# JiaB.net
KiCad netlist of a schematic drawn in EAGLE
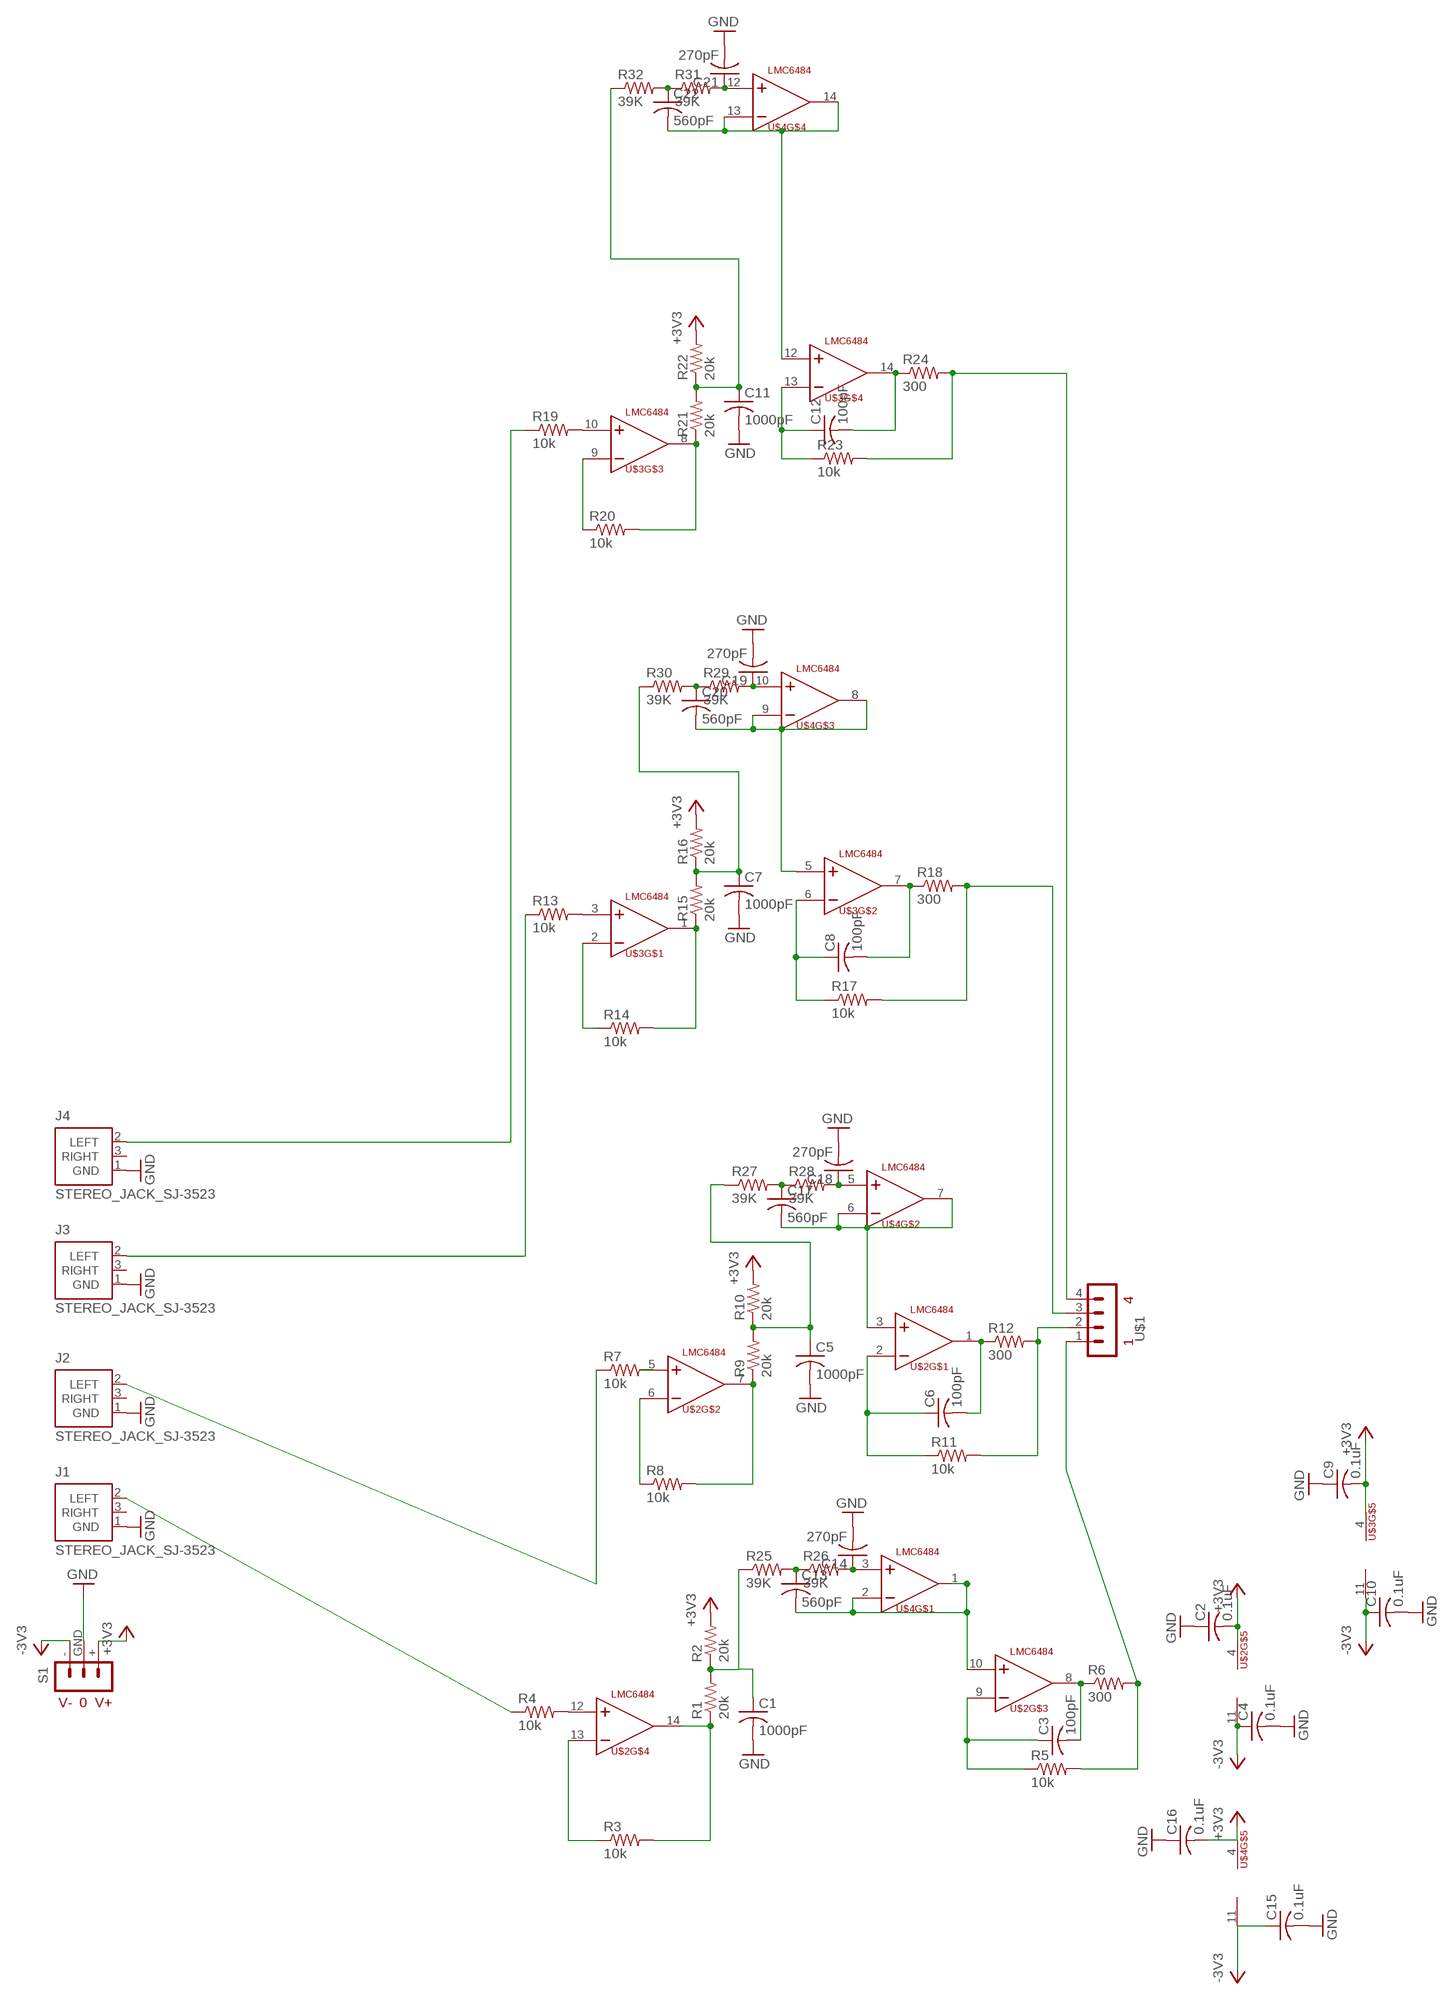
[diagram p0: schematic, sheet 1]

(export (version "E")
  (design (tool "Eeschema 10.0.6"))
  (components
    (comp (ref "C1")
      (value "1000pF")
      (footprint "eagle-import:C025-025X050")
      (libsource (lib "eagle-import") (part "resistor_C-US025-025X050"))
    )
    (comp (ref "C2")
      (value "0.1uF")
      (footprint "eagle-import:C025-025X050")
      (libsource (lib "eagle-import") (part "resistor_C-US025-025X050"))
    )
    (comp (ref "C3")
      (value "100pF")
      (footprint "eagle-import:C025-025X050")
      (libsource (lib "eagle-import") (part "resistor_C-US025-025X050"))
    )
    (comp (ref "C4")
      (value "0.1uF")
      (footprint "eagle-import:C025-025X050")
      (libsource (lib "eagle-import") (part "resistor_C-US025-025X050"))
    )
    (comp (ref "C5")
      (value "1000pF")
      (footprint "eagle-import:C025-025X050")
      (libsource (lib "eagle-import") (part "resistor_C-US025-025X050"))
    )
    (comp (ref "C6")
      (value "100pF")
      (footprint "eagle-import:C025-025X050")
      (libsource (lib "eagle-import") (part "resistor_C-US025-025X050"))
    )
    (comp (ref "C7")
      (value "1000pF")
      (footprint "eagle-import:C025-025X050")
      (libsource (lib "eagle-import") (part "resistor_C-US025-025X050"))
    )
    (comp (ref "C8")
      (value "100pF")
      (footprint "eagle-import:C025-025X050")
      (libsource (lib "eagle-import") (part "resistor_C-US025-025X050"))
    )
    (comp (ref "C9")
      (value "0.1uF")
      (footprint "eagle-import:C025-025X050")
      (libsource (lib "eagle-import") (part "resistor_C-US025-025X050"))
    )
    (comp (ref "C10")
      (value "0.1uF")
      (footprint "eagle-import:C025-025X050")
      (libsource (lib "eagle-import") (part "resistor_C-US025-025X050"))
    )
    (comp (ref "C11")
      (value "1000pF")
      (footprint "eagle-import:C025-025X050")
      (libsource (lib "eagle-import") (part "resistor_C-US025-025X050"))
    )
    (comp (ref "C12")
      (value "100pF")
      (footprint "eagle-import:C025-025X050")
      (libsource (lib "eagle-import") (part "resistor_C-US025-025X050"))
    )
    (comp (ref "C13")
      (value "560pF")
      (footprint "eagle-import:C025-025X050")
      (libsource (lib "eagle-import") (part "C-US025-025X050"))
    )
    (comp (ref "C14")
      (value "270pF")
      (footprint "eagle-import:C025-025X050")
      (libsource (lib "eagle-import") (part "C-US025-025X050"))
    )
    (comp (ref "C15")
      (value "0.1uF")
      (footprint "eagle-import:C025-025X050")
      (libsource (lib "eagle-import") (part "resistor_C-US025-025X050"))
    )
    (comp (ref "C16")
      (value "0.1uF")
      (footprint "eagle-import:C025-025X050")
      (libsource (lib "eagle-import") (part "resistor_C-US025-025X050"))
    )
    (comp (ref "C17")
      (value "560pF")
      (footprint "eagle-import:C025-025X050")
      (libsource (lib "eagle-import") (part "C-US025-025X050"))
    )
    (comp (ref "C18")
      (value "270pF")
      (footprint "eagle-import:C025-025X050")
      (libsource (lib "eagle-import") (part "C-US025-025X050"))
    )
    (comp (ref "C19")
      (value "270pF")
      (footprint "eagle-import:C025-025X050")
      (libsource (lib "eagle-import") (part "C-US025-025X050"))
    )
    (comp (ref "C20")
      (value "560pF")
      (footprint "eagle-import:C025-025X050")
      (libsource (lib "eagle-import") (part "C-US025-025X050"))
    )
    (comp (ref "C21")
      (value "270pF")
      (footprint "eagle-import:C025-025X050")
      (libsource (lib "eagle-import") (part "C-US025-025X050"))
    )
    (comp (ref "C22")
      (value "560pF")
      (footprint "eagle-import:C025-025X050")
      (libsource (lib "eagle-import") (part "C-US025-025X050"))
    )
    (comp (ref "J1")
      (value "STEREO_JACK_SJ-3523")
      (footprint "eagle-import:SJ-3523")
      (libsource (lib "eagle-import") (part "STEREO_JACK_SJ-3523"))
    )
    (comp (ref "J2")
      (value "STEREO_JACK_SJ-3523")
      (footprint "eagle-import:SJ-3523")
      (libsource (lib "eagle-import") (part "STEREO_JACK_SJ-3523"))
    )
    (comp (ref "J3")
      (value "STEREO_JACK_SJ-3523")
      (footprint "eagle-import:SJ-3523")
      (libsource (lib "eagle-import") (part "STEREO_JACK_SJ-3523"))
    )
    (comp (ref "J4")
      (value "STEREO_JACK_SJ-3523")
      (footprint "eagle-import:SJ-3523")
      (libsource (lib "eagle-import") (part "STEREO_JACK_SJ-3523"))
    )
    (comp (ref "R1")
      (value "20k")
      (footprint "eagle-import:0204_7")
      (libsource (lib "eagle-import") (part "resistor_R-US_0204/7"))
    )
    (comp (ref "R2")
      (value "20k")
      (footprint "eagle-import:0204_7")
      (libsource (lib "eagle-import") (part "resistor_R-US_0204/7"))
    )
    (comp (ref "R3")
      (value "10k")
      (footprint "eagle-import:0204_7")
      (libsource (lib "eagle-import") (part "resistor_R-US_0204/7"))
    )
    (comp (ref "R4")
      (value "10k")
      (footprint "eagle-import:0204_7")
      (libsource (lib "eagle-import") (part "resistor_R-US_0204/7"))
    )
    (comp (ref "R5")
      (value "10k")
      (footprint "eagle-import:0204_7")
      (libsource (lib "eagle-import") (part "resistor_R-US_0204/7"))
    )
    (comp (ref "R6")
      (value "300")
      (footprint "eagle-import:0204_7")
      (libsource (lib "eagle-import") (part "resistor_R-US_0204/7"))
    )
    (comp (ref "R7")
      (value "10k")
      (footprint "eagle-import:0204_7")
      (libsource (lib "eagle-import") (part "resistor_R-US_0204/7"))
    )
    (comp (ref "R8")
      (value "10k")
      (footprint "eagle-import:0204_7")
      (libsource (lib "eagle-import") (part "resistor_R-US_0204/7"))
    )
    (comp (ref "R9")
      (value "20k")
      (footprint "eagle-import:0204_7")
      (libsource (lib "eagle-import") (part "resistor_R-US_0204/7"))
    )
    (comp (ref "R10")
      (value "20k")
      (footprint "eagle-import:0204_7")
      (libsource (lib "eagle-import") (part "resistor_R-US_0204/7"))
    )
    (comp (ref "R11")
      (value "10k")
      (footprint "eagle-import:0204_7")
      (libsource (lib "eagle-import") (part "resistor_R-US_0204/7"))
    )
    (comp (ref "R12")
      (value "300")
      (footprint "eagle-import:0204_7")
      (libsource (lib "eagle-import") (part "resistor_R-US_0204/7"))
    )
    (comp (ref "R13")
      (value "10k")
      (footprint "eagle-import:0204_7")
      (libsource (lib "eagle-import") (part "resistor_R-US_0204/7"))
    )
    (comp (ref "R14")
      (value "10k")
      (footprint "eagle-import:0204_7")
      (libsource (lib "eagle-import") (part "resistor_R-US_0204/7"))
    )
    (comp (ref "R15")
      (value "20k")
      (footprint "eagle-import:0204_7")
      (libsource (lib "eagle-import") (part "resistor_R-US_0204/7"))
    )
    (comp (ref "R16")
      (value "20k")
      (footprint "eagle-import:0204_7")
      (libsource (lib "eagle-import") (part "resistor_R-US_0204/7"))
    )
    (comp (ref "R17")
      (value "10k")
      (footprint "eagle-import:0204_7")
      (libsource (lib "eagle-import") (part "resistor_R-US_0204/7"))
    )
    (comp (ref "R18")
      (value "300")
      (footprint "eagle-import:0204_7")
      (libsource (lib "eagle-import") (part "resistor_R-US_0204/7"))
    )
    (comp (ref "R19")
      (value "10k")
      (footprint "eagle-import:0204_7")
      (libsource (lib "eagle-import") (part "resistor_R-US_0204/7"))
    )
    (comp (ref "R20")
      (value "10k")
      (footprint "eagle-import:0204_7")
      (libsource (lib "eagle-import") (part "resistor_R-US_0204/7"))
    )
    (comp (ref "R21")
      (value "20k")
      (footprint "eagle-import:0204_7")
      (libsource (lib "eagle-import") (part "resistor_R-US_0204/7"))
    )
    (comp (ref "R22")
      (value "20k")
      (footprint "eagle-import:0204_7")
      (libsource (lib "eagle-import") (part "resistor_R-US_0204/7"))
    )
    (comp (ref "R23")
      (value "10k")
      (footprint "eagle-import:0204_7")
      (libsource (lib "eagle-import") (part "resistor_R-US_0204/7"))
    )
    (comp (ref "R24")
      (value "300")
      (footprint "eagle-import:0204_7")
      (libsource (lib "eagle-import") (part "resistor_R-US_0204/7"))
    )
    (comp (ref "R25")
      (value "39K")
      (footprint "eagle-import:0204_7")
      (libsource (lib "eagle-import") (part "R-US_0204/7"))
    )
    (comp (ref "R26")
      (value "39K")
      (footprint "eagle-import:0204_7")
      (libsource (lib "eagle-import") (part "R-US_0204/7"))
    )
    (comp (ref "R27")
      (value "39K")
      (footprint "eagle-import:0204_7")
      (libsource (lib "eagle-import") (part "R-US_0204/7"))
    )
    (comp (ref "R28")
      (value "39K")
      (footprint "eagle-import:0204_7")
      (libsource (lib "eagle-import") (part "R-US_0204/7"))
    )
    (comp (ref "R29")
      (value "39K")
      (footprint "eagle-import:0204_7")
      (libsource (lib "eagle-import") (part "R-US_0204/7"))
    )
    (comp (ref "R30")
      (value "39K")
      (footprint "eagle-import:0204_7")
      (libsource (lib "eagle-import") (part "R-US_0204/7"))
    )
    (comp (ref "R31")
      (value "39K")
      (footprint "eagle-import:0204_7")
      (libsource (lib "eagle-import") (part "R-US_0204/7"))
    )
    (comp (ref "R32")
      (value "39K")
      (footprint "eagle-import:0204_7")
      (libsource (lib "eagle-import") (part "R-US_0204/7"))
    )
    (comp (ref "S1")
      (value "TERMINAL_BLOCK_3_+/-3.3V")
      (footprint "eagle-import:TERMINAL_BLOCK_3.5MM_3")
      (libsource (lib "eagle-import") (part "TERMINAL_BLOCK_3_+/-3.3V"))
    )
    (comp (ref "U$1")
      (value "TERMINAL-BLOCK-4")
      (footprint "eagle-import:TERMINAL-BLOCK-4")
      (libsource (lib "eagle-import") (part "TERMINAL-BLOCK-4"))
    )
    (comp (ref "U$2")
      (value "LMC6484")
      (footprint "eagle-import:DIL14")
      (libsource (lib "eagle-import") (part "LMC6484"))
    )
    (comp (ref "U$3")
      (value "LMC6484")
      (footprint "eagle-import:DIL14")
      (libsource (lib "eagle-import") (part "LMC6484"))
    )
    (comp (ref "U$4")
      (value "LMC6484")
      (footprint "eagle-import:DIL14")
      (libsource (lib "eagle-import") (part "LMC6484"))
    )
  )
  (nets
    (net (code "1") (name "+3V3") (class "Default")
      (node (ref "C16") (pin "2") (pinfunction "2_2") (pintype "passive"))
      (node (ref "C2") (pin "2") (pinfunction "2_2") (pintype "passive"))
      (node (ref "C9") (pin "2") (pinfunction "2_2") (pintype "passive"))
      (node (ref "R10") (pin "2") (pinfunction "2_2") (pintype "passive"))
      (node (ref "R16") (pin "2") (pinfunction "2_2") (pintype "passive"))
      (node (ref "R2") (pin "2") (pinfunction "2_2") (pintype "passive"))
      (node (ref "R22") (pin "2") (pinfunction "2_2") (pintype "passive"))
      (node (ref "S1") (pin "+") (pinfunction "+_+") (pintype "passive"))
      (node (ref "U$2") (pin "4") (pinfunction "VCC+_4") (pintype "power_in"))
      (node (ref "U$3") (pin "4") (pinfunction "VCC+_4") (pintype "power_in"))
      (node (ref "U$4") (pin "4") (pinfunction "VCC+_4") (pintype "power_in"))
    )
    (net (code "2") (name "-3V3") (class "Default")
      (node (ref "C10") (pin "1") (pinfunction "1_1") (pintype "passive"))
      (node (ref "C15") (pin "1") (pinfunction "1_1") (pintype "passive"))
      (node (ref "C4") (pin "1") (pinfunction "1_1") (pintype "passive"))
      (node (ref "S1") (pin "-") (pinfunction "-_-") (pintype "passive"))
      (node (ref "U$2") (pin "11") (pinfunction "VCC-_11") (pintype "power_in"))
      (node (ref "U$3") (pin "11") (pinfunction "VCC-_11") (pintype "power_in"))
      (node (ref "U$4") (pin "11") (pinfunction "VCC-_11") (pintype "power_in"))
    )
    (net (code "3") (name "GND") (class "Default")
      (node (ref "C1") (pin "2") (pinfunction "2_2") (pintype "passive"))
      (node (ref "C10") (pin "2") (pinfunction "2_2") (pintype "passive"))
      (node (ref "C11") (pin "2") (pinfunction "2_2") (pintype "passive"))
      (node (ref "C14") (pin "2") (pinfunction "2_2") (pintype "passive"))
      (node (ref "C15") (pin "2") (pinfunction "2_2") (pintype "passive"))
      (node (ref "C16") (pin "1") (pinfunction "1_1") (pintype "passive"))
      (node (ref "C18") (pin "2") (pinfunction "2_2") (pintype "passive"))
      (node (ref "C19") (pin "2") (pinfunction "2_2") (pintype "passive"))
      (node (ref "C2") (pin "1") (pinfunction "1_1") (pintype "passive"))
      (node (ref "C21") (pin "2") (pinfunction "2_2") (pintype "passive"))
      (node (ref "C4") (pin "2") (pinfunction "2_2") (pintype "passive"))
      (node (ref "C5") (pin "2") (pinfunction "2_2") (pintype "passive"))
      (node (ref "C7") (pin "2") (pinfunction "2_2") (pintype "passive"))
      (node (ref "C9") (pin "1") (pinfunction "1_1") (pintype "passive"))
      (node (ref "J1") (pin "1") (pinfunction "GND_1") (pintype "power_in"))
      (node (ref "J2") (pin "1") (pinfunction "GND_1") (pintype "power_in"))
      (node (ref "J3") (pin "1") (pinfunction "GND_1") (pintype "power_in"))
      (node (ref "J4") (pin "1") (pinfunction "GND_1") (pintype "power_in"))
      (node (ref "S1") (pin "GND") (pinfunction "GND_GND") (pintype "passive"))
    )
    (net (code "4") (name "Net-(C1-Pad1)") (class "Default")
      (node (ref "C1") (pin "1") (pinfunction "1_1") (pintype "passive"))
      (node (ref "R1") (pin "2") (pinfunction "2_2") (pintype "passive"))
      (node (ref "R2") (pin "1") (pinfunction "1_1") (pintype "passive"))
      (node (ref "R25") (pin "1") (pinfunction "1_1") (pintype "passive"))
    )
    (net (code "5") (name "Net-(C5-Pad1)") (class "Default")
      (node (ref "C5") (pin "1") (pinfunction "1_1") (pintype "passive"))
      (node (ref "R10") (pin "1") (pinfunction "1_1") (pintype "passive"))
      (node (ref "R27") (pin "1") (pinfunction "1_1") (pintype "passive"))
      (node (ref "R9") (pin "2") (pinfunction "2_2") (pintype "passive"))
    )
    (net (code "6") (name "Net-(C7-Pad1)") (class "Default")
      (node (ref "C7") (pin "1") (pinfunction "1_1") (pintype "passive"))
      (node (ref "R15") (pin "2") (pinfunction "2_2") (pintype "passive"))
      (node (ref "R16") (pin "1") (pinfunction "1_1") (pintype "passive"))
      (node (ref "R30") (pin "1") (pinfunction "1_1") (pintype "passive"))
    )
    (net (code "7") (name "Net-(C11-Pad1)") (class "Default")
      (node (ref "C11") (pin "1") (pinfunction "1_1") (pintype "passive"))
      (node (ref "R21") (pin "2") (pinfunction "2_2") (pintype "passive"))
      (node (ref "R22") (pin "1") (pinfunction "1_1") (pintype "passive"))
      (node (ref "R32") (pin "1") (pinfunction "1_1") (pintype "passive"))
    )
    (net (code "8") (name "Net-(C13-Pad1)") (class "Default")
      (node (ref "C13") (pin "1") (pinfunction "1_1") (pintype "passive"))
      (node (ref "R25") (pin "2") (pinfunction "2_2") (pintype "passive"))
      (node (ref "R26") (pin "1") (pinfunction "1_1") (pintype "passive"))
    )
    (net (code "9") (name "Net-(C17-Pad1)") (class "Default")
      (node (ref "C17") (pin "1") (pinfunction "1_1") (pintype "passive"))
      (node (ref "R27") (pin "2") (pinfunction "2_2") (pintype "passive"))
      (node (ref "R28") (pin "1") (pinfunction "1_1") (pintype "passive"))
    )
    (net (code "10") (name "Net-(C20-Pad1)") (class "Default")
      (node (ref "C20") (pin "1") (pinfunction "1_1") (pintype "passive"))
      (node (ref "R29") (pin "1") (pinfunction "1_1") (pintype "passive"))
      (node (ref "R30") (pin "2") (pinfunction "2_2") (pintype "passive"))
    )
    (net (code "11") (name "Net-(C22-Pad1)") (class "Default")
      (node (ref "C22") (pin "1") (pinfunction "1_1") (pintype "passive"))
      (node (ref "R31") (pin "1") (pinfunction "1_1") (pintype "passive"))
      (node (ref "R32") (pin "2") (pinfunction "2_2") (pintype "passive"))
    )
    (net (code "12") (name "Net-(J1-LEFT)") (class "Default")
      (node (ref "J1") (pin "2") (pinfunction "LEFT_2") (pintype "output"))
      (node (ref "R4") (pin "1") (pinfunction "1_1") (pintype "passive"))
    )
    (net (code "13") (name "Net-(J2-LEFT)") (class "Default")
      (node (ref "J2") (pin "2") (pinfunction "LEFT_2") (pintype "output"))
      (node (ref "R7") (pin "1") (pinfunction "1_1") (pintype "passive"))
    )
    (net (code "14") (name "Net-(J3-LEFT)") (class "Default")
      (node (ref "J3") (pin "2") (pinfunction "LEFT_2") (pintype "output"))
      (node (ref "R13") (pin "1") (pinfunction "1_1") (pintype "passive"))
    )
    (net (code "15") (name "Net-(J4-LEFT)") (class "Default")
      (node (ref "J4") (pin "2") (pinfunction "LEFT_2") (pintype "output"))
      (node (ref "R19") (pin "1") (pinfunction "1_1") (pintype "passive"))
    )
    (net (code "16") (name "Net-(R5-Pad2)") (class "Default")
      (node (ref "R5") (pin "2") (pinfunction "2_2") (pintype "passive"))
      (node (ref "R6") (pin "2") (pinfunction "2_2") (pintype "passive"))
      (node (ref "U$1") (pin "1") (pinfunction "1_1") (pintype "passive"))
    )
    (net (code "17") (name "Net-(R11-Pad2)") (class "Default")
      (node (ref "R11") (pin "2") (pinfunction "2_2") (pintype "passive"))
      (node (ref "R12") (pin "2") (pinfunction "2_2") (pintype "passive"))
      (node (ref "U$1") (pin "2") (pinfunction "2_2") (pintype "passive"))
    )
    (net (code "18") (name "Net-(R17-Pad2)") (class "Default")
      (node (ref "R17") (pin "2") (pinfunction "2_2") (pintype "passive"))
      (node (ref "R18") (pin "2") (pinfunction "2_2") (pintype "passive"))
      (node (ref "U$1") (pin "3") (pinfunction "3_3") (pintype "passive"))
    )
    (net (code "19") (name "Net-(R23-Pad2)") (class "Default")
      (node (ref "R23") (pin "2") (pinfunction "2_2") (pintype "passive"))
      (node (ref "R24") (pin "2") (pinfunction "2_2") (pintype "passive"))
      (node (ref "U$1") (pin "4") (pinfunction "4_4") (pintype "passive"))
    )
    (net (code "20") (name "Net-(U$2A-IN+)") (class "Default")
      (node (ref "C17") (pin "2") (pinfunction "2_2") (pintype "passive"))
      (node (ref "U$2") (pin "3") (pinfunction "IN+_3") (pintype "input"))
      (node (ref "U$4") (pin "6") (pinfunction "IN-_6") (pintype "input"))
      (node (ref "U$4") (pin "7") (pinfunction "OUT_7") (pintype "output"))
    )
    (net (code "21") (name "Net-(U$2A-IN-)") (class "Default")
      (node (ref "C6") (pin "1") (pinfunction "1_1") (pintype "passive"))
      (node (ref "R11") (pin "1") (pinfunction "1_1") (pintype "passive"))
      (node (ref "U$2") (pin "2") (pinfunction "IN-_2") (pintype "input"))
    )
    (net (code "22") (name "Net-(U$2A-OUT)") (class "Default")
      (node (ref "C6") (pin "2") (pinfunction "2_2") (pintype "passive"))
      (node (ref "R12") (pin "1") (pinfunction "1_1") (pintype "passive"))
      (node (ref "U$2") (pin "1") (pinfunction "OUT_1") (pintype "output"))
    )
    (net (code "23") (name "Net-(U$2B-IN+)") (class "Default")
      (node (ref "R7") (pin "2") (pinfunction "2_2") (pintype "passive"))
      (node (ref "U$2") (pin "5") (pinfunction "IN+_5") (pintype "input"))
    )
    (net (code "24") (name "Net-(U$2B-IN-)") (class "Default")
      (node (ref "R8") (pin "1") (pinfunction "1_1") (pintype "passive"))
      (node (ref "U$2") (pin "6") (pinfunction "IN-_6") (pintype "input"))
    )
    (net (code "25") (name "Net-(U$2B-OUT)") (class "Default")
      (node (ref "R8") (pin "2") (pinfunction "2_2") (pintype "passive"))
      (node (ref "R9") (pin "1") (pinfunction "1_1") (pintype "passive"))
      (node (ref "U$2") (pin "7") (pinfunction "OUT_7") (pintype "output"))
    )
    (net (code "26") (name "Net-(U$2C-IN+)") (class "Default")
      (node (ref "C13") (pin "2") (pinfunction "2_2") (pintype "passive"))
      (node (ref "U$2") (pin "10") (pinfunction "IN+_10") (pintype "input"))
      (node (ref "U$4") (pin "1") (pinfunction "OUT_1") (pintype "output"))
      (node (ref "U$4") (pin "2") (pinfunction "IN-_2") (pintype "input"))
    )
    (net (code "27") (name "Net-(U$2C-IN-)") (class "Default")
      (node (ref "C3") (pin "1") (pinfunction "1_1") (pintype "passive"))
      (node (ref "R5") (pin "1") (pinfunction "1_1") (pintype "passive"))
      (node (ref "U$2") (pin "9") (pinfunction "IN-_9") (pintype "input"))
    )
    (net (code "28") (name "Net-(U$2C-OUT)") (class "Default")
      (node (ref "C3") (pin "2") (pinfunction "2_2") (pintype "passive"))
      (node (ref "R6") (pin "1") (pinfunction "1_1") (pintype "passive"))
      (node (ref "U$2") (pin "8") (pinfunction "OUT_8") (pintype "output"))
    )
    (net (code "29") (name "Net-(U$2D-IN+)") (class "Default")
      (node (ref "R4") (pin "2") (pinfunction "2_2") (pintype "passive"))
      (node (ref "U$2") (pin "12") (pinfunction "IN+_12") (pintype "input"))
    )
    (net (code "30") (name "Net-(U$2D-IN-)") (class "Default")
      (node (ref "R3") (pin "1") (pinfunction "1_1") (pintype "passive"))
      (node (ref "U$2") (pin "13") (pinfunction "IN-_13") (pintype "input"))
    )
    (net (code "31") (name "Net-(U$2D-OUT)") (class "Default")
      (node (ref "R1") (pin "1") (pinfunction "1_1") (pintype "passive"))
      (node (ref "R3") (pin "2") (pinfunction "2_2") (pintype "passive"))
      (node (ref "U$2") (pin "14") (pinfunction "OUT_14") (pintype "output"))
    )
    (net (code "32") (name "Net-(U$3A-IN+)") (class "Default")
      (node (ref "R13") (pin "2") (pinfunction "2_2") (pintype "passive"))
      (node (ref "U$3") (pin "3") (pinfunction "IN+_3") (pintype "input"))
    )
    (net (code "33") (name "Net-(U$3A-IN-)") (class "Default")
      (node (ref "R14") (pin "1") (pinfunction "1_1") (pintype "passive"))
      (node (ref "U$3") (pin "2") (pinfunction "IN-_2") (pintype "input"))
    )
    (net (code "34") (name "Net-(U$3A-OUT)") (class "Default")
      (node (ref "R14") (pin "2") (pinfunction "2_2") (pintype "passive"))
      (node (ref "R15") (pin "1") (pinfunction "1_1") (pintype "passive"))
      (node (ref "U$3") (pin "1") (pinfunction "OUT_1") (pintype "output"))
    )
    (net (code "35") (name "Net-(U$3B-IN+)") (class "Default")
      (node (ref "C20") (pin "2") (pinfunction "2_2") (pintype "passive"))
      (node (ref "U$3") (pin "5") (pinfunction "IN+_5") (pintype "input"))
      (node (ref "U$4") (pin "8") (pinfunction "OUT_8") (pintype "output"))
      (node (ref "U$4") (pin "9") (pinfunction "IN-_9") (pintype "input"))
    )
    (net (code "36") (name "Net-(U$3B-IN-)") (class "Default")
      (node (ref "C8") (pin "1") (pinfunction "1_1") (pintype "passive"))
      (node (ref "R17") (pin "1") (pinfunction "1_1") (pintype "passive"))
      (node (ref "U$3") (pin "6") (pinfunction "IN-_6") (pintype "input"))
    )
    (net (code "37") (name "Net-(U$3B-OUT)") (class "Default")
      (node (ref "C8") (pin "2") (pinfunction "2_2") (pintype "passive"))
      (node (ref "R18") (pin "1") (pinfunction "1_1") (pintype "passive"))
      (node (ref "U$3") (pin "7") (pinfunction "OUT_7") (pintype "output"))
    )
    (net (code "38") (name "Net-(U$3C-IN+)") (class "Default")
      (node (ref "R19") (pin "2") (pinfunction "2_2") (pintype "passive"))
      (node (ref "U$3") (pin "10") (pinfunction "IN+_10") (pintype "input"))
    )
    (net (code "39") (name "Net-(U$3C-IN-)") (class "Default")
      (node (ref "R20") (pin "1") (pinfunction "1_1") (pintype "passive"))
      (node (ref "U$3") (pin "9") (pinfunction "IN-_9") (pintype "input"))
    )
    (net (code "40") (name "Net-(U$3C-OUT)") (class "Default")
      (node (ref "R20") (pin "2") (pinfunction "2_2") (pintype "passive"))
      (node (ref "R21") (pin "1") (pinfunction "1_1") (pintype "passive"))
      (node (ref "U$3") (pin "8") (pinfunction "OUT_8") (pintype "output"))
    )
    (net (code "41") (name "Net-(U$3D-IN+)") (class "Default")
      (node (ref "C22") (pin "2") (pinfunction "2_2") (pintype "passive"))
      (node (ref "U$3") (pin "12") (pinfunction "IN+_12") (pintype "input"))
      (node (ref "U$4") (pin "13") (pinfunction "IN-_13") (pintype "input"))
      (node (ref "U$4") (pin "14") (pinfunction "OUT_14") (pintype "output"))
    )
    (net (code "42") (name "Net-(U$3D-IN-)") (class "Default")
      (node (ref "C12") (pin "1") (pinfunction "1_1") (pintype "passive"))
      (node (ref "R23") (pin "1") (pinfunction "1_1") (pintype "passive"))
      (node (ref "U$3") (pin "13") (pinfunction "IN-_13") (pintype "input"))
    )
    (net (code "43") (name "Net-(U$3D-OUT)") (class "Default")
      (node (ref "C12") (pin "2") (pinfunction "2_2") (pintype "passive"))
      (node (ref "R24") (pin "1") (pinfunction "1_1") (pintype "passive"))
      (node (ref "U$3") (pin "14") (pinfunction "OUT_14") (pintype "output"))
    )
    (net (code "44") (name "Net-(U$4A-IN+)") (class "Default")
      (node (ref "C14") (pin "1") (pinfunction "1_1") (pintype "passive"))
      (node (ref "R26") (pin "2") (pinfunction "2_2") (pintype "passive"))
      (node (ref "U$4") (pin "3") (pinfunction "IN+_3") (pintype "input"))
    )
    (net (code "45") (name "Net-(U$4B-IN+)") (class "Default")
      (node (ref "C18") (pin "1") (pinfunction "1_1") (pintype "passive"))
      (node (ref "R28") (pin "2") (pinfunction "2_2") (pintype "passive"))
      (node (ref "U$4") (pin "5") (pinfunction "IN+_5") (pintype "input"))
    )
    (net (code "46") (name "Net-(U$4C-IN+)") (class "Default")
      (node (ref "C19") (pin "1") (pinfunction "1_1") (pintype "passive"))
      (node (ref "R29") (pin "2") (pinfunction "2_2") (pintype "passive"))
      (node (ref "U$4") (pin "10") (pinfunction "IN+_10") (pintype "input"))
    )
    (net (code "47") (name "Net-(U$4D-IN+)") (class "Default")
      (node (ref "C21") (pin "1") (pinfunction "1_1") (pintype "passive"))
      (node (ref "R31") (pin "2") (pinfunction "2_2") (pintype "passive"))
      (node (ref "U$4") (pin "12") (pinfunction "IN+_12") (pintype "input"))
    )
    (net (code "48") (name "unconnected-(J1-RIGHT-Pad3)") (class "Default")
      (node (ref "J1") (pin "3") (pinfunction "RIGHT_3") (pintype "output"))
    )
    (net (code "49") (name "unconnected-(J2-RIGHT-Pad3)") (class "Default")
      (node (ref "J2") (pin "3") (pinfunction "RIGHT_3") (pintype "output"))
    )
    (net (code "50") (name "unconnected-(J3-RIGHT-Pad3)") (class "Default")
      (node (ref "J3") (pin "3") (pinfunction "RIGHT_3") (pintype "output"))
    )
    (net (code "51") (name "unconnected-(J4-RIGHT-Pad3)") (class "Default")
      (node (ref "J4") (pin "3") (pinfunction "RIGHT_3") (pintype "output"))
    )
  )
)
